# MCU_STM32F407ZGT6.net
KiCad netlist of a schematic drawn in Altium Designer
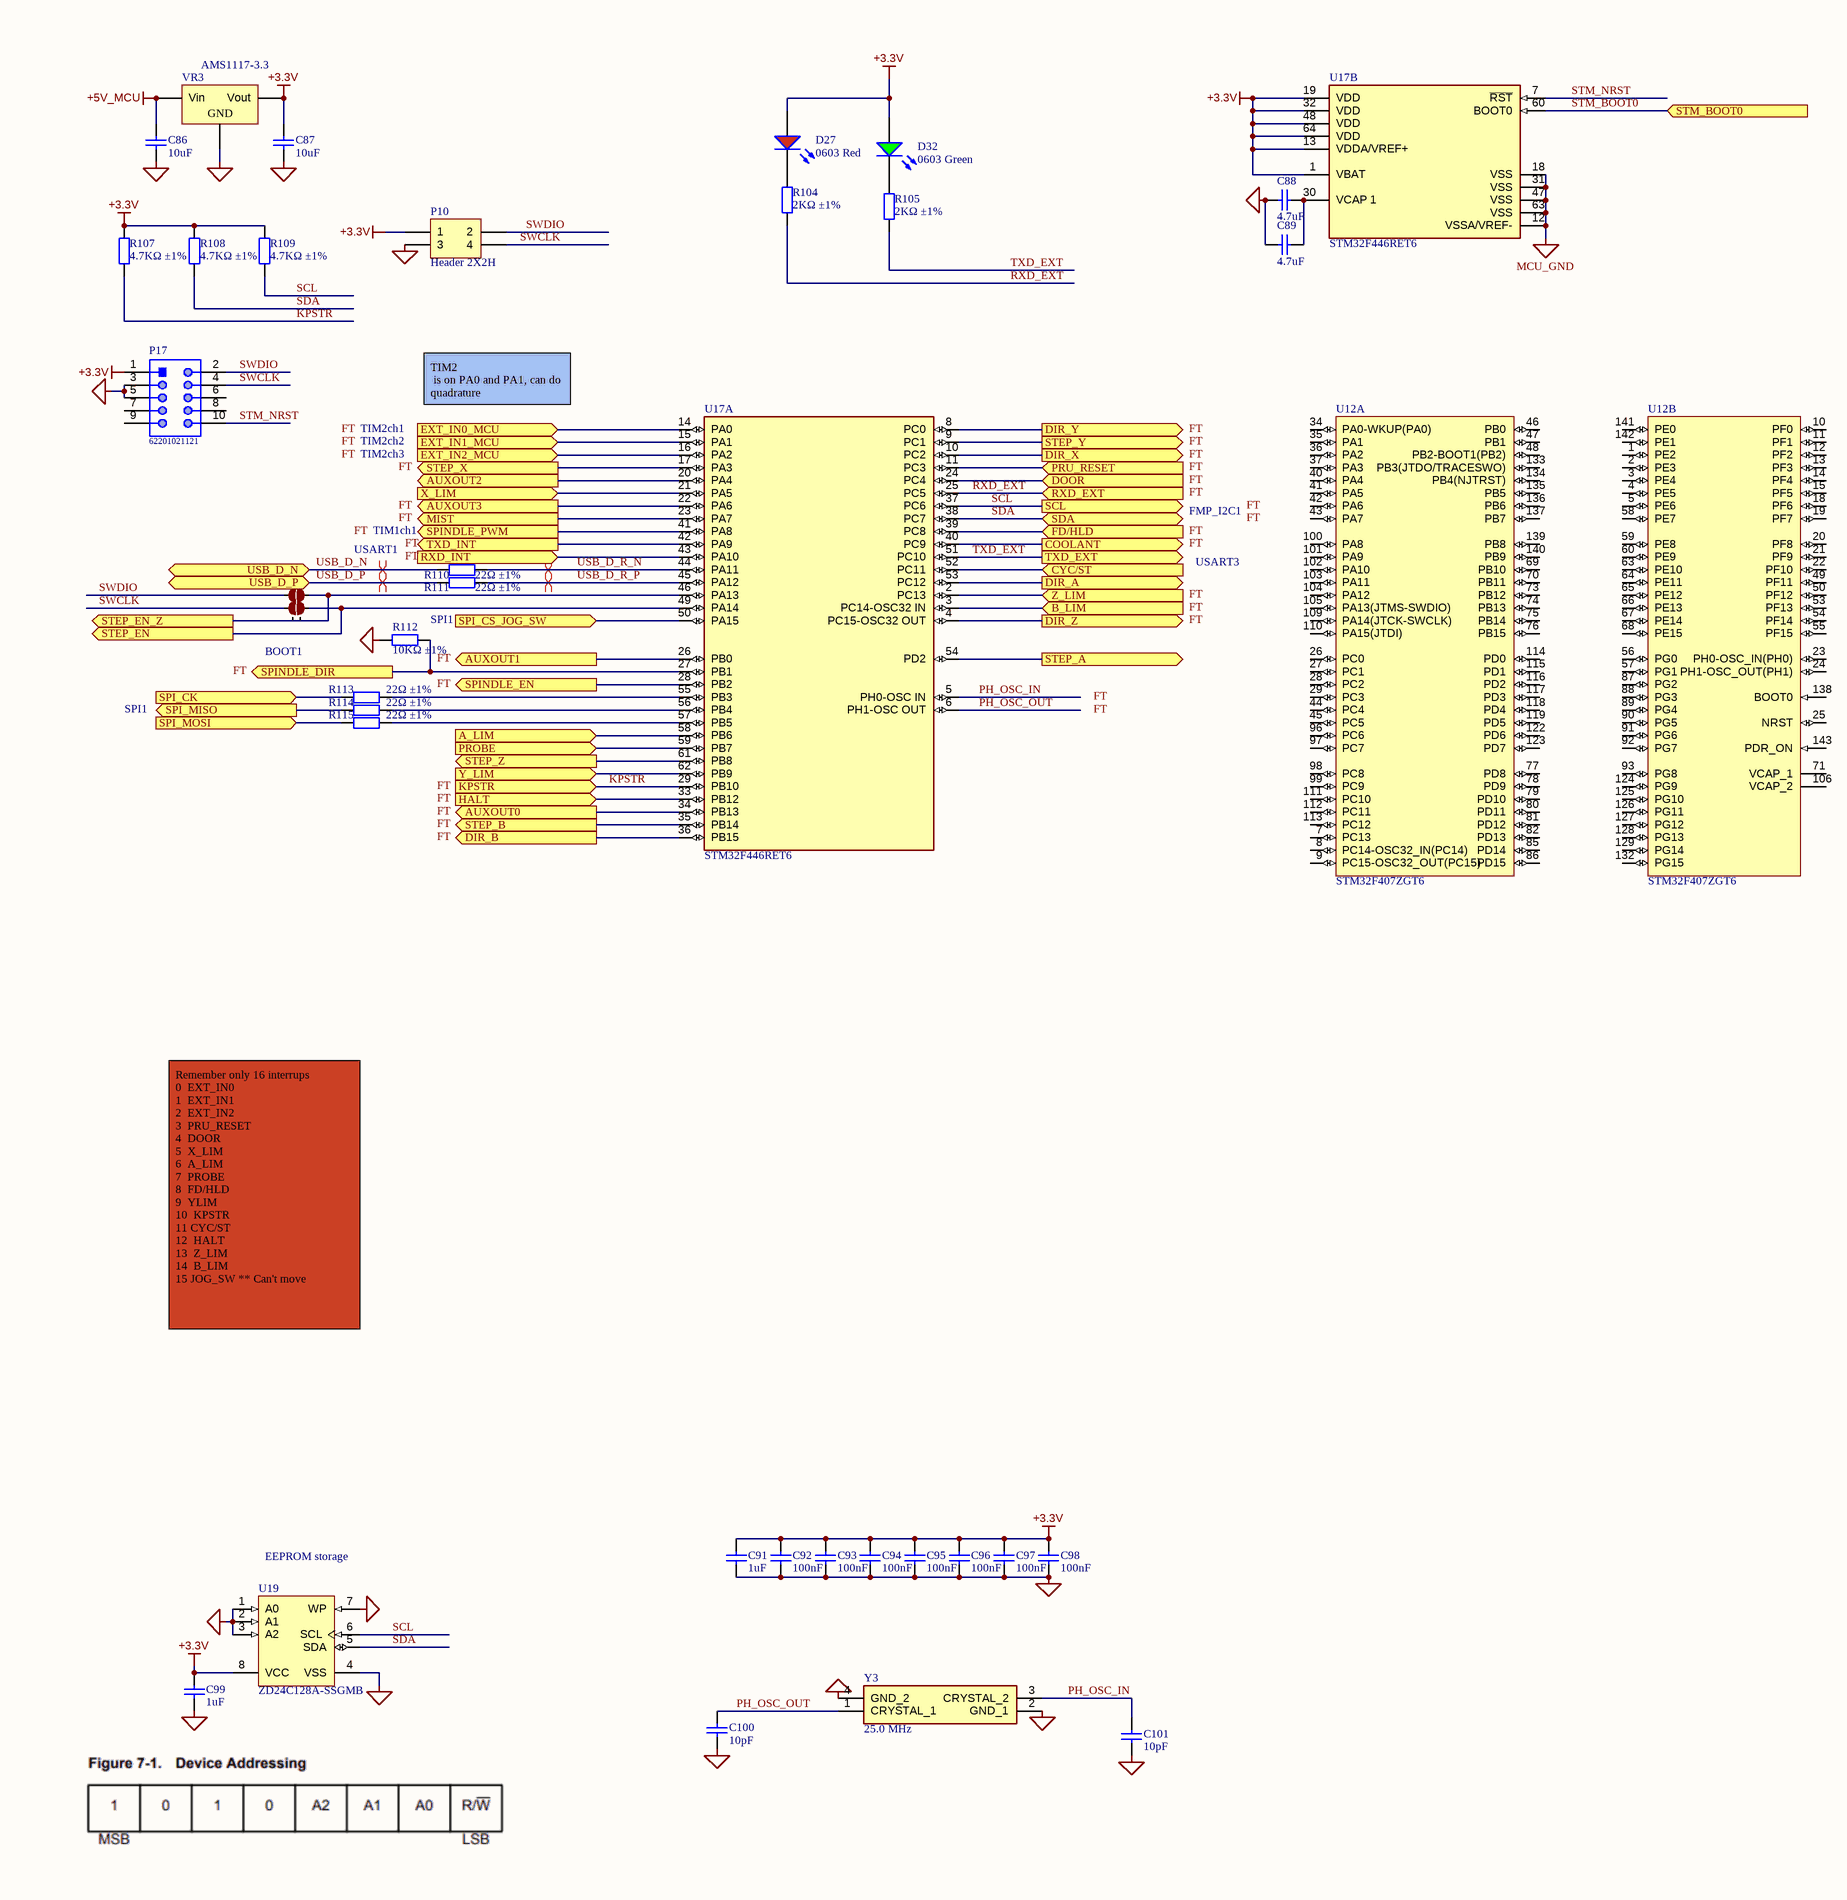
[diagram p0: MCU_STM32F407ZGT6.SchDoc, left]
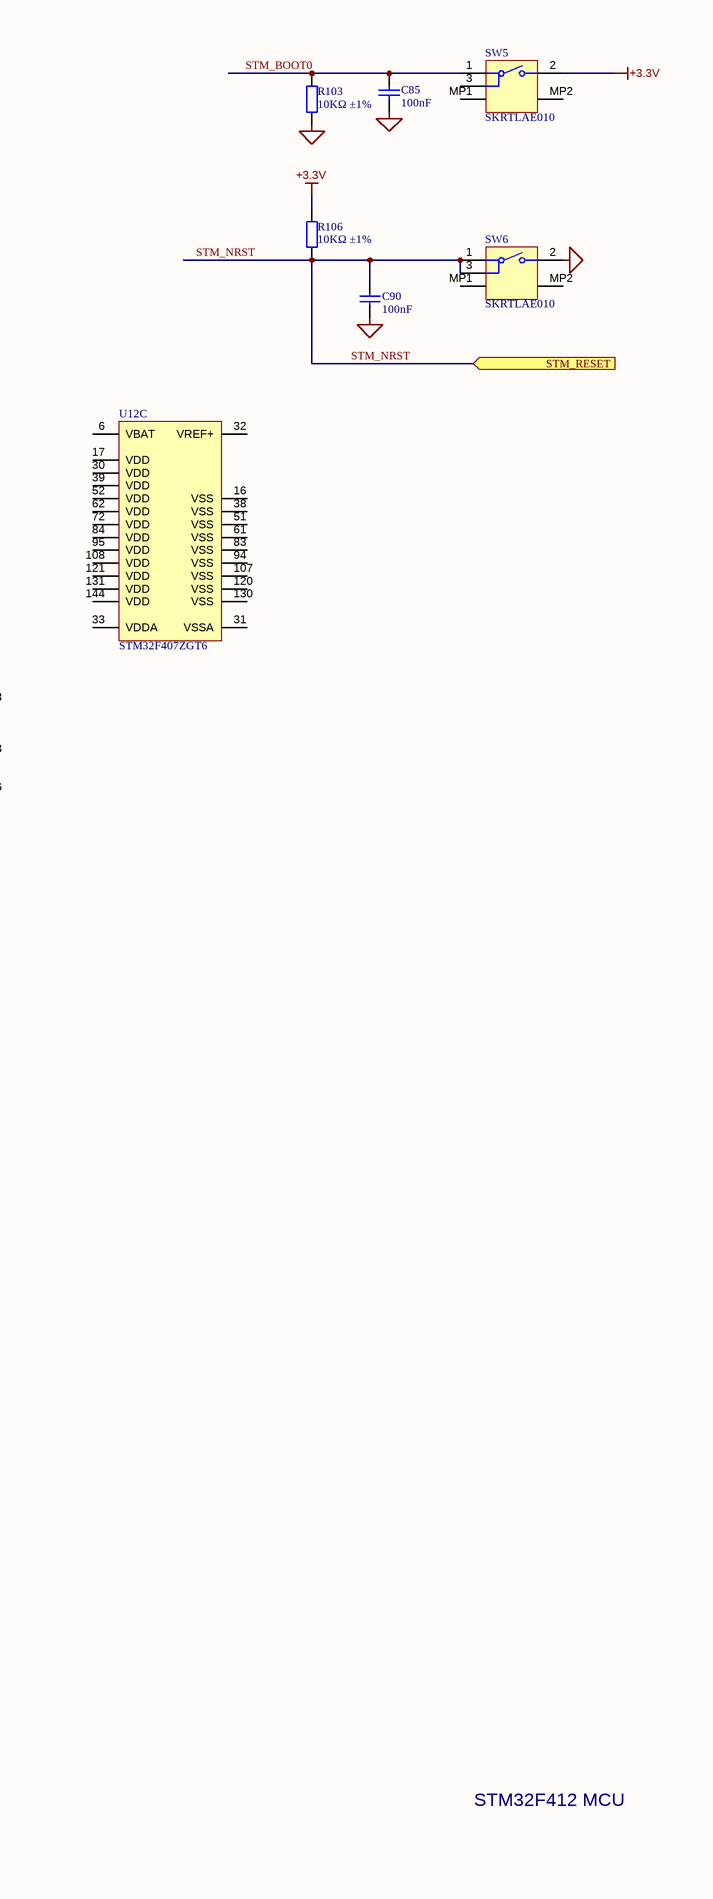
[diagram p1: MCU_STM32F407ZGT6.SchDoc, right]

(export (version "E")
  (design (tool "Eeschema 10.0.6"))
  (components
    (comp (ref "C85")
      (value "100nF")
      (footprint "0603_C")
      (description "Chip capacitors")
      (fields (field (name "MANUFACTURER") "YAGEO") (field (name "PARTNUMBER") "CC0603KRX7R9BB104"))
      (libsource (lib "Cap") (part "0603 100nF (104) 10% 50V"))
    )
    (comp (ref "C86")
      (value "10uF")
      (footprint "1206_C")
      (description "Chip capacitors")
      (fields
        (field (name "MANUFACTURER") "Samsung Electro-Mechanics")
        (field (name "PARTNUMBER") "CL31A106KBHNNNE")
      )
      (libsource (lib "Cap") (part "1206 10uF (106) 10% 50V"))
    )
    (comp (ref "C87")
      (value "10uF")
      (footprint "1206_C")
      (description "Chip capacitors")
      (fields
        (field (name "MANUFACTURER") "Samsung Electro-Mechanics")
        (field (name "PARTNUMBER") "CL31A106KBHNNNE")
      )
      (libsource (lib "Cap") (part "1206 10uF (106) 10% 50V"))
    )
    (comp (ref "C88")
      (value "4.7uF")
      (footprint "0603_C")
      (description "Chip capacitors")
      (fields
        (field (name "MANUFACTURER") "Samsung Electro-Mechanics")
        (field (name "PARTNUMBER") "CL10A475KO8NNNC")
      )
      (libsource (lib "Cap") (part "0603 4.7uF (475) 10% 16V"))
    )
    (comp (ref "C89")
      (value "4.7uF")
      (footprint "0603_C")
      (description "Chip capacitors")
      (fields
        (field (name "MANUFACTURER") "Samsung Electro-Mechanics")
        (field (name "PARTNUMBER") "CL10A475KO8NNNC")
      )
      (libsource (lib "Cap") (part "0603 4.7uF (475) 10% 16V"))
    )
    (comp (ref "C90")
      (value "100nF")
      (footprint "0603_C")
      (description "Chip capacitors")
      (fields (field (name "MANUFACTURER") "YAGEO") (field (name "PARTNUMBER") "CC0603KRX7R9BB104"))
      (libsource (lib "Cap") (part "0603 100nF (104) 10% 50V"))
    )
    (comp (ref "C91")
      (value "1uF")
      (footprint "0603_C")
      (description "Chip capacitors")
      (fields
        (field (name "MANUFACTURER") "Samsung Electro-Mechanics")
        (field (name "PARTNUMBER") "CL10A105KB8NNNC")
      )
      (libsource (lib "Cap") (part "0603 1uF (105) 10% 50V"))
    )
    (comp (ref "C92")
      (value "100nF")
      (footprint "0603_C")
      (description "Chip capacitors")
      (fields (field (name "MANUFACTURER") "YAGEO") (field (name "PARTNUMBER") "CC0603KRX7R9BB104"))
      (libsource (lib "Cap") (part "0603 100nF (104) 10% 50V"))
    )
    (comp (ref "C93")
      (value "100nF")
      (footprint "0603_C")
      (description "Chip capacitors")
      (fields (field (name "MANUFACTURER") "YAGEO") (field (name "PARTNUMBER") "CC0603KRX7R9BB104"))
      (libsource (lib "Cap") (part "0603 100nF (104) 10% 50V"))
    )
    (comp (ref "C94")
      (value "100nF")
      (footprint "0603_C")
      (description "Chip capacitors")
      (fields (field (name "MANUFACTURER") "YAGEO") (field (name "PARTNUMBER") "CC0603KRX7R9BB104"))
      (libsource (lib "Cap") (part "0603 100nF (104) 10% 50V"))
    )
    (comp (ref "C95")
      (value "100nF")
      (footprint "0603_C")
      (description "Chip capacitors")
      (fields (field (name "MANUFACTURER") "YAGEO") (field (name "PARTNUMBER") "CC0603KRX7R9BB104"))
      (libsource (lib "Cap") (part "0603 100nF (104) 10% 50V"))
    )
    (comp (ref "C96")
      (value "100nF")
      (footprint "0603_C")
      (description "Chip capacitors")
      (fields (field (name "MANUFACTURER") "YAGEO") (field (name "PARTNUMBER") "CC0603KRX7R9BB104"))
      (libsource (lib "Cap") (part "0603 100nF (104) 10% 50V"))
    )
    (comp (ref "C97")
      (value "100nF")
      (footprint "0603_C")
      (description "Chip capacitors")
      (fields (field (name "MANUFACTURER") "YAGEO") (field (name "PARTNUMBER") "CC0603KRX7R9BB104"))
      (libsource (lib "Cap") (part "0603 100nF (104) 10% 50V"))
    )
    (comp (ref "C98")
      (value "100nF")
      (footprint "0603_C")
      (description "Chip capacitors")
      (fields (field (name "MANUFACTURER") "YAGEO") (field (name "PARTNUMBER") "CC0603KRX7R9BB104"))
      (libsource (lib "Cap") (part "0603 100nF (104) 10% 50V"))
    )
    (comp (ref "C99")
      (value "1uF")
      (footprint "0603_C")
      (description "Chip capacitors")
      (fields
        (field (name "MANUFACTURER") "Samsung Electro-Mechanics")
        (field (name "PARTNUMBER") "CL10A105KB8NNNC")
      )
      (libsource (lib "Cap") (part "0603 1uF (105) 10% 50V"))
    )
    (comp (ref "C100")
      (value "10pF")
      (footprint "0603_C")
      (description "Chip capacitors")
      (fields
        (field (name "MANUFACTURER") "Samsung Electro-Mechanics")
        (field (name "PARTNUMBER") "CL10C100JB8NNNC")
      )
      (libsource (lib "Cap") (part "0603 10pF (100) 5% 50V"))
    )
    (comp (ref "C101")
      (value "10pF")
      (footprint "0603_C")
      (description "Chip capacitors")
      (fields
        (field (name "MANUFACTURER") "Samsung Electro-Mechanics")
        (field (name "PARTNUMBER") "CL10C100JB8NNNC")
      )
      (libsource (lib "Cap") (part "0603 10pF (100) 5% 50V"))
    )
    (comp (ref "D27")
      (value "0603 Red")
      (footprint "0603_LED_S1")
      (description "LED")
      (libsource (lib "LED") (part "0603 LED Red"))
    )
    (comp (ref "D32")
      (value "0603 Green")
      (footprint "0603_LED_S1")
      (description "LED")
      (libsource (lib "LED") (part "0603 LED Green"))
    )
    (comp (ref "J17")
      (value "2 way net solder junction - Normally Open")
      (footprint "2waySolder_NO")
      (libsource (lib "PrintNC_GRBLHAL_Breakout") (part "2waySolderNO"))
    )
    (comp (ref "J18")
      (value "2 way net solder junction - Normally Open")
      (footprint "2waySolder_NO")
      (libsource (lib "PrintNC_GRBLHAL_Breakout") (part "2waySolderNO"))
    )
    (comp (ref "P10")
      (value "Header 2X2H")
      (footprint "HDR2X2H")
      (description "Header, 2-Pin, Dual row, Right Angle")
      (fields (field (name "PUBLISHER") "Altium Limited"))
      (libsource (lib "Miscellaneous Connectors") (part "Header 2X2H"))
    )
    (comp (ref "P17")
      (value "62201021121")
      (footprint "62201021121")
      (description "THT Vertical Pin Header WR-PHD, Pitch 1.27 mm, Dual Row, 10 pins")
      (fields (field (name "MANUFACTURER") "Wurth Elektronik") (field (name "PUBLISHER") "WurthElektronik"))
      (libsource (lib "Altium Content Vault") (part "WE-CN-2P-M-R10"))
    )
    (comp (ref "R103")
      (value "10KΩ ±1%")
      (footprint "0603_R")
      (description "Chip resistor")
      (fields (field (name "MANUFACTURER") "Uniroyal Elec") (field (name "PARTNUMBER") "0603WAF1002T5E"))
      (libsource (lib "") (part "0603 10K (1002) 1%_1"))
    )
    (comp (ref "R104")
      (value "2KΩ ±1%")
      (footprint "0603_R")
      (description "Chip resistor")
      (fields (field (name "MANUFACTURER") "Uniroyal Elec") (field (name "PARTNUMBER") "0603WAF2001T5E"))
      (libsource (lib "RES") (part "0603 2K (2001) 1%"))
    )
    (comp (ref "R105")
      (value "2KΩ ±1%")
      (footprint "0603_R")
      (description "Chip resistor")
      (fields (field (name "MANUFACTURER") "Uniroyal Elec") (field (name "PARTNUMBER") "0603WAF2001T5E"))
      (libsource (lib "RES") (part "0603 2K (2001) 1%"))
    )
    (comp (ref "R106")
      (value "10KΩ ±1%")
      (footprint "0603_R")
      (description "Chip resistor")
      (fields (field (name "MANUFACTURER") "Uniroyal Elec") (field (name "PARTNUMBER") "0603WAF1002T5E"))
      (libsource (lib "") (part "0603 10K (1002) 1%_1"))
    )
    (comp (ref "R107")
      (value "4.7KΩ ±1%")
      (footprint "0603_R")
      (description "Chip resistor")
      (fields (field (name "MANUFACTURER") "Uniroyal Elec") (field (name "PARTNUMBER") "0603WAF4701T5E"))
      (libsource (lib "RES") (part "0603 4.7K (4701) 1%"))
    )
    (comp (ref "R108")
      (value "4.7KΩ ±1%")
      (footprint "0603_R")
      (description "Chip resistor")
      (fields (field (name "MANUFACTURER") "Uniroyal Elec") (field (name "PARTNUMBER") "0603WAF4701T5E"))
      (libsource (lib "RES") (part "0603 4.7K (4701) 1%"))
    )
    (comp (ref "R109")
      (value "4.7KΩ ±1%")
      (footprint "0603_R")
      (description "Chip resistor")
      (fields (field (name "MANUFACTURER") "Uniroyal Elec") (field (name "PARTNUMBER") "0603WAF4701T5E"))
      (libsource (lib "RES") (part "0603 4.7K (4701) 1%"))
    )
    (comp (ref "R110")
      (value "22Ω ±1%")
      (footprint "0603_R")
      (description "Chip resistor")
      (fields (field (name "MANUFACTURER") "Uniroyal Elec") (field (name "PARTNUMBER") "0603WAF220JT5E"))
      (libsource (lib "RES") (part "0603 22R (22R0) 1%"))
    )
    (comp (ref "R111")
      (value "22Ω ±1%")
      (footprint "0603_R")
      (description "Chip resistor")
      (fields (field (name "MANUFACTURER") "Uniroyal Elec") (field (name "PARTNUMBER") "0603WAF220JT5E"))
      (libsource (lib "RES") (part "0603 22R (22R0) 1%"))
    )
    (comp (ref "R112")
      (value "10KΩ ±1%")
      (footprint "0603_R")
      (description "Chip resistor")
      (fields (field (name "MANUFACTURER") "Uniroyal Elec") (field (name "PARTNUMBER") "0603WAF1002T5E"))
      (libsource (lib "RES") (part "0603 10K (1002) 1%"))
    )
    (comp (ref "R113")
      (value "22Ω ±1%")
      (footprint "0603_R")
      (description "Chip resistor")
      (fields (field (name "MANUFACTURER") "Uniroyal Elec") (field (name "PARTNUMBER") "0603WAF220JT5E"))
      (libsource (lib "RES") (part "0603 22R (22R0) 1%"))
    )
    (comp (ref "R114")
      (value "22Ω ±1%")
      (footprint "0603_R")
      (description "Chip resistor")
      (fields (field (name "MANUFACTURER") "Uniroyal Elec") (field (name "PARTNUMBER") "0603WAF220JT5E"))
      (libsource (lib "RES") (part "0603 22R (22R0) 1%"))
    )
    (comp (ref "R115")
      (value "22Ω ±1%")
      (footprint "0603_R")
      (description "Chip resistor")
      (fields (field (name "MANUFACTURER") "Uniroyal Elec") (field (name "PARTNUMBER") "0603WAF220JT5E"))
      (libsource (lib "RES") (part "0603 22R (22R0) 1%"))
    )
    (comp (ref "SW5")
      (value "SKRTLAE010")
      (footprint "ALPS-SKRTLAE010_V")
      (description "Side Push Type, 250 V, -40 to 90 degC, 3-Pin SMD, RoHS, Tape and Reel")
      (fields (field (name "MANUFACTURER") "ALPS"))
      (libsource (lib "Altium Content Vault") (part "SW_SPST-3_A"))
    )
    (comp (ref "SW6")
      (value "SKRTLAE010")
      (footprint "ALPS-SKRTLAE010_V")
      (description "Side Push Type, 250 V, -40 to 90 degC, 3-Pin SMD, RoHS, Tape and Reel")
      (fields (field (name "MANUFACTURER") "ALPS"))
      (libsource (lib "Altium Content Vault") (part "SW_SPST-3_A"))
    )
    (comp (ref "U12")
      (value "STM32F407ZGT6")
      (footprint "STM-LQFP144_L")
      (fields (field (name "MANUFACTURER") "STMicroelectronics") (field (name "PARTNUMBER") "STM32F407ZET6"))
      (libsource (lib "Universal_CNC_Breakout") (part "STM32F407ZGT6"))
    )
    (comp (ref "U17")
      (value "STM32F446RET6")
      (footprint "FP-LQFP64-5W-IPC_B")
      (description "IC MCU 32BIT 512KB FLASH 64LQFP")
      (fields
        (field (name "OCTOPART") "https://octopart.com/stm32f446ret6-stmicroelectronics-52642920")
        (field (name "MANUFACTURER") "STMicroelectronics")
      )
      (libsource (lib "Universal_CNC_Breakout") (part "STM32F446RET6"))
    )
    (comp (ref "U19")
      (value "ZD24C128A-SSGMB")
      (footprint "SOIC-SN8_L")
      (description "IC EEPROM 128KBIT I2C 8SOIC")
      (libsource (lib "PrintNC_GRBLHAL_Breakout") (part "MEM-SEEPROM-34AA02-IL8"))
    )
    (comp (ref "VR3")
      (value "AMS1117-3.3")
      (footprint "SOT-223")
      (description "Vout=3.3V 1A 72dB@(120Hz) (LDO)")
      (libsource (lib "LDO") (part "SOT-223 AMS1117-3.3"))
    )
    (comp (ref "Y3")
      (value "25.0 MHz")
      (footprint "SamacSys:YSX321SL")
      (description "Crystal or Oscillator")
      (fields (field (name "MANUFACTURER_PART_NUMBER") "X322525MSB4SI"))
      (libsource (lib "*") (part "YSX321SL"))
    )
  )
  (nets
    (net (code "1") (name "+3.3V") (class "Default")
      (node (ref "C87") (pin "2") (pinfunction "2_2") (pintype "passive"))
      (node (ref "C91") (pin "2") (pinfunction "2_2") (pintype "passive"))
      (node (ref "C92") (pin "2") (pinfunction "2_2") (pintype "passive"))
      (node (ref "C93") (pin "2") (pinfunction "2_2") (pintype "passive"))
      (node (ref "C94") (pin "2") (pinfunction "2_2") (pintype "passive"))
      (node (ref "C95") (pin "2") (pinfunction "2_2") (pintype "passive"))
      (node (ref "C96") (pin "2") (pinfunction "2_2") (pintype "passive"))
      (node (ref "C97") (pin "2") (pinfunction "2_2") (pintype "passive"))
      (node (ref "C98") (pin "2") (pinfunction "2_2") (pintype "passive"))
      (node (ref "C99") (pin "2") (pinfunction "2_2") (pintype "passive"))
      (node (ref "D27") (pin "A") (pinfunction "A_A") (pintype "passive"))
      (node (ref "D32") (pin "A") (pinfunction "A_A") (pintype "passive"))
      (node (ref "P10") (pin "1") (pinfunction "1_1") (pintype "passive"))
      (node (ref "P17") (pin "1") (pinfunction "1_1") (pintype "passive"))
      (node (ref "R106") (pin "1") (pinfunction "1_1") (pintype "passive"))
      (node (ref "R107") (pin "2") (pinfunction "2_2") (pintype "passive"))
      (node (ref "R108") (pin "2") (pinfunction "2_2") (pintype "passive"))
      (node (ref "R109") (pin "2") (pinfunction "2_2") (pintype "passive"))
      (node (ref "SW5") (pin "2") (pinfunction "2_2") (pintype "passive"))
      (node (ref "U17") (pin "1") (pinfunction "VBAT_1") (pintype "power_in"))
      (node (ref "U17") (pin "13") (pinfunction "VDDA/VREF+_13") (pintype "power_in"))
      (node (ref "U17") (pin "19") (pinfunction "VDD_19") (pintype "power_in"))
      (node (ref "U17") (pin "32") (pinfunction "VDD_32") (pintype "power_in"))
      (node (ref "U17") (pin "48") (pinfunction "VDD_48") (pintype "power_in"))
      (node (ref "U17") (pin "64") (pinfunction "VDD_64") (pintype "power_in"))
      (node (ref "U19") (pin "8") (pinfunction "VCC_8") (pintype "power_in"))
      (node (ref "VR3") (pin "2") (pinfunction "Vout_2") (pintype "passive"))
    )
    (net (code "2") (name "+5V_MCU") (class "Default")
      (node (ref "C86") (pin "2") (pinfunction "2_2") (pintype "passive"))
      (node (ref "VR3") (pin "3") (pinfunction "Vin_3") (pintype "passive"))
    )
    (net (code "3") (name "/AUXOUT0") (class "Default")
      (node (ref "U17") (pin "34") (pinfunction "PB13_34") (pintype "bidirectional"))
    )
    (net (code "4") (name "/AUXOUT1") (class "Default")
      (node (ref "U17") (pin "26") (pinfunction "PB0_26") (pintype "bidirectional"))
    )
    (net (code "5") (name "/AUXOUT2") (class "Default")
      (node (ref "U17") (pin "20") (pinfunction "PA4_20") (pintype "bidirectional"))
    )
    (net (code "6") (name "/AUXOUT3") (class "Default")
      (node (ref "U17") (pin "22") (pinfunction "PA6_22") (pintype "bidirectional"))
    )
    (net (code "7") (name "/A_LIM") (class "Default")
      (node (ref "U17") (pin "58") (pinfunction "PB6_58") (pintype "bidirectional"))
    )
    (net (code "8") (name "/B_LIM") (class "Default")
      (node (ref "U17") (pin "3") (pinfunction "PC14-OSC32_IN_3") (pintype "bidirectional"))
    )
    (net (code "9") (name "/COOLANT") (class "Default")
      (node (ref "U17") (pin "40") (pinfunction "PC9_40") (pintype "bidirectional"))
    )
    (net (code "10") (name "/CYC{slash}ST") (class "Default")
      (node (ref "U17") (pin "52") (pinfunction "PC11_52") (pintype "bidirectional"))
    )
    (net (code "11") (name "/DIR_A") (class "Default")
      (node (ref "U17") (pin "53") (pinfunction "PC12_53") (pintype "bidirectional"))
    )
    (net (code "12") (name "/DIR_B") (class "Default")
      (node (ref "U17") (pin "36") (pinfunction "PB15_36") (pintype "bidirectional"))
    )
    (net (code "13") (name "/DIR_X") (class "Default")
      (node (ref "U17") (pin "10") (pinfunction "PC2_10") (pintype "bidirectional"))
    )
    (net (code "14") (name "/DIR_Y") (class "Default")
      (node (ref "U17") (pin "8") (pinfunction "PC0_8") (pintype "bidirectional"))
    )
    (net (code "15") (name "/DIR_Z") (class "Default")
      (node (ref "U17") (pin "4") (pinfunction "PC15-OSC32_OUT_4") (pintype "bidirectional"))
    )
    (net (code "16") (name "/DOOR") (class "Default")
      (node (ref "U17") (pin "24") (pinfunction "PC4_24") (pintype "bidirectional"))
    )
    (net (code "17") (name "/EXT_IN0_MCU") (class "Default")
      (node (ref "U17") (pin "14") (pinfunction "PA0_14") (pintype "bidirectional"))
    )
    (net (code "18") (name "/EXT_IN1_MCU") (class "Default")
      (node (ref "U17") (pin "15") (pinfunction "PA1_15") (pintype "bidirectional"))
    )
    (net (code "19") (name "/EXT_IN2_MCU") (class "Default")
      (node (ref "U17") (pin "16") (pinfunction "PA2_16") (pintype "bidirectional"))
    )
    (net (code "20") (name "/FD{slash}HLD") (class "Default")
      (node (ref "U17") (pin "39") (pinfunction "PC8_39") (pintype "bidirectional"))
    )
    (net (code "21") (name "/HALT") (class "Default")
      (node (ref "U17") (pin "33") (pinfunction "PB12_33") (pintype "bidirectional"))
    )
    (net (code "22") (name "/KPSTR") (class "Default")
      (node (ref "R107") (pin "1") (pinfunction "1_1") (pintype "passive"))
      (node (ref "U17") (pin "29") (pinfunction "PB10_29") (pintype "bidirectional"))
    )
    (net (code "23") (name "/MIST") (class "Default")
      (node (ref "U17") (pin "23") (pinfunction "PA7_23") (pintype "bidirectional"))
    )
    (net (code "24") (name "/PH_OSC_IN") (class "Default")
      (node (ref "C101") (pin "2") (pinfunction "2_2") (pintype "passive"))
      (node (ref "U17") (pin "5") (pinfunction "PH0-OSC_IN_5") (pintype "bidirectional"))
      (node (ref "Y3") (pin "3") (pinfunction "CRYSTAL_2_3") (pintype "passive"))
    )
    (net (code "25") (name "/PH_OSC_OUT") (class "Default")
      (node (ref "C100") (pin "2") (pinfunction "2_2") (pintype "passive"))
      (node (ref "U17") (pin "6") (pinfunction "PH1-OSC_OUT_6") (pintype "bidirectional"))
      (node (ref "Y3") (pin "1") (pinfunction "CRYSTAL_1_1") (pintype "passive"))
    )
    (net (code "26") (name "/PROBE") (class "Default")
      (node (ref "U17") (pin "59") (pinfunction "PB7_59") (pintype "bidirectional"))
    )
    (net (code "27") (name "/PRU_RESET") (class "Default")
      (node (ref "U17") (pin "11") (pinfunction "PC3_11") (pintype "bidirectional"))
    )
    (net (code "28") (name "/RXD_EXT") (class "Default")
      (node (ref "R104") (pin "1") (pinfunction "1_1") (pintype "passive"))
      (node (ref "U17") (pin "25") (pinfunction "PC5_25") (pintype "bidirectional"))
    )
    (net (code "29") (name "/RXD_INT") (class "Default")
      (node (ref "U17") (pin "43") (pinfunction "PA10_43") (pintype "bidirectional"))
    )
    (net (code "30") (name "/SCL") (class "Default")
      (node (ref "R109") (pin "1") (pinfunction "1_1") (pintype "passive"))
      (node (ref "U17") (pin "37") (pinfunction "PC6_37") (pintype "bidirectional"))
      (node (ref "U19") (pin "6") (pinfunction "SCL_6") (pintype "input"))
    )
    (net (code "31") (name "/SDA") (class "Default")
      (node (ref "R108") (pin "1") (pinfunction "1_1") (pintype "passive"))
      (node (ref "U17") (pin "38") (pinfunction "PC7_38") (pintype "bidirectional"))
      (node (ref "U19") (pin "5") (pinfunction "SDA_5") (pintype "bidirectional"))
    )
    (net (code "32") (name "/SPINDLE_DIR") (class "Default")
      (node (ref "R112") (pin "2") (pinfunction "2_2") (pintype "passive"))
      (node (ref "U17") (pin "27") (pinfunction "PB1_27") (pintype "bidirectional"))
    )
    (net (code "33") (name "/SPINDLE_EN") (class "Default")
      (node (ref "U17") (pin "28") (pinfunction "PB2_28") (pintype "bidirectional"))
    )
    (net (code "34") (name "/SPINDLE_PWM") (class "Default")
      (node (ref "U17") (pin "41") (pinfunction "PA8_41") (pintype "bidirectional"))
    )
    (net (code "35") (name "/SPI_CK") (class "Default")
      (node (ref "R113") (pin "2") (pinfunction "2_2") (pintype "passive"))
    )
    (net (code "36") (name "/SPI_CS_JOG_SW") (class "Default")
      (node (ref "U17") (pin "50") (pinfunction "PA15_50") (pintype "bidirectional"))
    )
    (net (code "37") (name "/SPI_MISO") (class "Default")
      (node (ref "R114") (pin "2") (pinfunction "2_2") (pintype "passive"))
    )
    (net (code "38") (name "/SPI_MOSI") (class "Default")
      (node (ref "R115") (pin "2") (pinfunction "2_2") (pintype "passive"))
    )
    (net (code "39") (name "/STEP_A") (class "Default")
      (node (ref "U17") (pin "54") (pinfunction "PD2_54") (pintype "bidirectional"))
    )
    (net (code "40") (name "/STEP_B") (class "Default")
      (node (ref "U17") (pin "35") (pinfunction "PB14_35") (pintype "bidirectional"))
    )
    (net (code "41") (name "/STEP_EN") (class "Default")
      (node (ref "J18") (pin "2") (pinfunction "2_2") (pintype "passive"))
      (node (ref "U17") (pin "49") (pinfunction "PA14_49") (pintype "bidirectional"))
    )
    (net (code "42") (name "/STEP_EN_Z") (class "Default")
      (node (ref "J17") (pin "2") (pinfunction "2_2") (pintype "passive"))
      (node (ref "U17") (pin "46") (pinfunction "PA13_46") (pintype "bidirectional"))
    )
    (net (code "43") (name "/STEP_X") (class "Default")
      (node (ref "U17") (pin "17") (pinfunction "PA3_17") (pintype "bidirectional"))
    )
    (net (code "44") (name "/STEP_Y") (class "Default")
      (node (ref "U17") (pin "9") (pinfunction "PC1_9") (pintype "bidirectional"))
    )
    (net (code "45") (name "/STEP_Z") (class "Default")
      (node (ref "U17") (pin "61") (pinfunction "PB8_61") (pintype "bidirectional"))
    )
    (net (code "46") (name "/STM_BOOT0") (class "Default")
      (node (ref "C85") (pin "2") (pinfunction "2_2") (pintype "passive"))
      (node (ref "R103") (pin "1") (pinfunction "1_1") (pintype "passive"))
      (node (ref "SW5") (pin "1") (pinfunction "1_1") (pintype "passive"))
      (node (ref "U17") (pin "60") (pinfunction "BOOT0_60") (pintype "input"))
    )
    (net (code "47") (name "/STM_NRST") (class "Default")
      (node (ref "C90") (pin "2") (pinfunction "2_2") (pintype "passive"))
      (node (ref "P17") (pin "10") (pinfunction "10_10") (pintype "passive"))
      (node (ref "R106") (pin "2") (pinfunction "2_2") (pintype "passive"))
      (node (ref "SW6") (pin "1") (pinfunction "1_1") (pintype "passive"))
      (node (ref "SW6") (pin "3") (pinfunction "3_3") (pintype "passive"))
      (node (ref "U17") (pin "7") (pinfunction "~{RST}_7") (pintype "input"))
    )
    (net (code "48") (name "/SWCLK") (class "Default")
      (node (ref "J18") (pin "1") (pinfunction "1_1") (pintype "passive"))
      (node (ref "P10") (pin "4") (pinfunction "4_4") (pintype "passive"))
      (node (ref "P17") (pin "4") (pinfunction "4_4") (pintype "passive"))
    )
    (net (code "49") (name "/SWDIO") (class "Default")
      (node (ref "J17") (pin "1") (pinfunction "1_1") (pintype "passive"))
      (node (ref "P10") (pin "2") (pinfunction "2_2") (pintype "passive"))
      (node (ref "P17") (pin "2") (pinfunction "2_2") (pintype "passive"))
    )
    (net (code "50") (name "/TXD_EXT") (class "Default")
      (node (ref "R105") (pin "1") (pinfunction "1_1") (pintype "passive"))
      (node (ref "U17") (pin "51") (pinfunction "PC10_51") (pintype "bidirectional"))
    )
    (net (code "51") (name "/TXD_INT") (class "Default")
      (node (ref "U17") (pin "42") (pinfunction "PA9_42") (pintype "bidirectional"))
    )
    (net (code "52") (name "/USB_D_N") (class "Default")
      (node (ref "R110") (pin "2") (pinfunction "2_2") (pintype "passive"))
    )
    (net (code "53") (name "/USB_D_P") (class "Default")
      (node (ref "R111") (pin "2") (pinfunction "2_2") (pintype "passive"))
    )
    (net (code "54") (name "/USB_D_R_N") (class "Default")
      (node (ref "R110") (pin "1") (pinfunction "1_1") (pintype "passive"))
      (node (ref "U17") (pin "44") (pinfunction "PA11_44") (pintype "bidirectional"))
    )
    (net (code "55") (name "/USB_D_R_P") (class "Default")
      (node (ref "R111") (pin "1") (pinfunction "1_1") (pintype "passive"))
      (node (ref "U17") (pin "45") (pinfunction "PA12_45") (pintype "bidirectional"))
    )
    (net (code "56") (name "/X_LIM") (class "Default")
      (node (ref "U17") (pin "21") (pinfunction "PA5_21") (pintype "bidirectional"))
    )
    (net (code "57") (name "/Y_LIM") (class "Default")
      (node (ref "U17") (pin "62") (pinfunction "PB9_62") (pintype "bidirectional"))
    )
    (net (code "58") (name "/Z_LIM") (class "Default")
      (node (ref "U17") (pin "2") (pinfunction "PC13_2") (pintype "bidirectional"))
    )
    (net (code "59") (name "MCU_GND") (class "Default")
      (node (ref "C100") (pin "1") (pinfunction "1_1") (pintype "passive"))
      (node (ref "C101") (pin "1") (pinfunction "1_1") (pintype "passive"))
      (node (ref "C85") (pin "1") (pinfunction "1_1") (pintype "passive"))
      (node (ref "C86") (pin "1") (pinfunction "1_1") (pintype "passive"))
      (node (ref "C87") (pin "1") (pinfunction "1_1") (pintype "passive"))
      (node (ref "C88") (pin "1") (pinfunction "1_1") (pintype "passive"))
      (node (ref "C89") (pin "1") (pinfunction "1_1") (pintype "passive"))
      (node (ref "C90") (pin "1") (pinfunction "1_1") (pintype "passive"))
      (node (ref "C91") (pin "1") (pinfunction "1_1") (pintype "passive"))
      (node (ref "C92") (pin "1") (pinfunction "1_1") (pintype "passive"))
      (node (ref "C93") (pin "1") (pinfunction "1_1") (pintype "passive"))
      (node (ref "C94") (pin "1") (pinfunction "1_1") (pintype "passive"))
      (node (ref "C95") (pin "1") (pinfunction "1_1") (pintype "passive"))
      (node (ref "C96") (pin "1") (pinfunction "1_1") (pintype "passive"))
      (node (ref "C97") (pin "1") (pinfunction "1_1") (pintype "passive"))
      (node (ref "C98") (pin "1") (pinfunction "1_1") (pintype "passive"))
      (node (ref "C99") (pin "1") (pinfunction "1_1") (pintype "passive"))
      (node (ref "P10") (pin "3") (pinfunction "3_3") (pintype "passive"))
      (node (ref "P17") (pin "3") (pinfunction "3_3") (pintype "passive"))
      (node (ref "P17") (pin "5") (pinfunction "5_5") (pintype "passive"))
      (node (ref "R103") (pin "2") (pinfunction "2_2") (pintype "passive"))
      (node (ref "R112") (pin "1") (pinfunction "1_1") (pintype "passive"))
      (node (ref "SW6") (pin "2") (pinfunction "2_2") (pintype "passive"))
      (node (ref "U17") (pin "12") (pinfunction "VSSA/VREF-_12") (pintype "power_in"))
      (node (ref "U17") (pin "18") (pinfunction "VSS_18") (pintype "power_in"))
      (node (ref "U17") (pin "31") (pinfunction "VSS_31") (pintype "power_in"))
      (node (ref "U17") (pin "47") (pinfunction "VSS_47") (pintype "power_in"))
      (node (ref "U17") (pin "63") (pinfunction "VSS_63") (pintype "power_in"))
      (node (ref "U19") (pin "1") (pinfunction "A0_1") (pintype "input"))
      (node (ref "U19") (pin "2") (pinfunction "A1_2") (pintype "input"))
      (node (ref "U19") (pin "3") (pinfunction "A2_3") (pintype "input"))
      (node (ref "U19") (pin "4") (pinfunction "VSS_4") (pintype "power_in"))
      (node (ref "U19") (pin "7") (pinfunction "WP_7") (pintype "input"))
      (node (ref "VR3") (pin "1") (pinfunction "GND_1") (pintype "passive"))
      (node (ref "Y3") (pin "2") (pinfunction "GND_1_2") (pintype "passive"))
      (node (ref "Y3") (pin "4") (pinfunction "GND_2_4") (pintype "passive"))
    )
    (net (code "60") (name "Net-(D27-PadK)") (class "Default")
      (node (ref "D27") (pin "K") (pinfunction "K_K") (pintype "passive"))
      (node (ref "R104") (pin "2") (pinfunction "2_2") (pintype "passive"))
    )
    (net (code "61") (name "Net-(D32-PadK)") (class "Default")
      (node (ref "D32") (pin "K") (pinfunction "K_K") (pintype "passive"))
      (node (ref "R105") (pin "2") (pinfunction "2_2") (pintype "passive"))
    )
    (net (code "62") (name "Net-(U17A-PB3)") (class "Default")
      (node (ref "R113") (pin "1") (pinfunction "1_1") (pintype "passive"))
      (node (ref "U17") (pin "55") (pinfunction "PB3_55") (pintype "bidirectional"))
    )
    (net (code "63") (name "Net-(U17A-PB4)") (class "Default")
      (node (ref "R114") (pin "1") (pinfunction "1_1") (pintype "passive"))
      (node (ref "U17") (pin "56") (pinfunction "PB4_56") (pintype "bidirectional"))
    )
    (net (code "64") (name "Net-(U17A-PB5)") (class "Default")
      (node (ref "R115") (pin "1") (pinfunction "1_1") (pintype "passive"))
      (node (ref "U17") (pin "57") (pinfunction "PB5_57") (pintype "bidirectional"))
    )
    (net (code "65") (name "Net-(U17B-VCAP_1)") (class "Default")
      (node (ref "C88") (pin "2") (pinfunction "2_2") (pintype "passive"))
      (node (ref "C89") (pin "2") (pinfunction "2_2") (pintype "passive"))
      (node (ref "U17") (pin "30") (pinfunction "VCAP_1_30") (pintype "power_in"))
    )
    (net (code "66") (name "unconnected-(P17-Pad6)") (class "Default")
      (node (ref "P17") (pin "6") (pinfunction "6_6") (pintype "passive"))
    )
    (net (code "67") (name "unconnected-(P17-Pad7)") (class "Default")
      (node (ref "P17") (pin "7") (pinfunction "7_7") (pintype "passive"))
    )
    (net (code "68") (name "unconnected-(P17-Pad8)") (class "Default")
      (node (ref "P17") (pin "8") (pinfunction "8_8") (pintype "passive"))
    )
    (net (code "69") (name "unconnected-(P17-Pad9)") (class "Default")
      (node (ref "P17") (pin "9") (pinfunction "9_9") (pintype "passive"))
    )
    (net (code "70") (name "unconnected-(SW5-Pad3)") (class "Default")
      (node (ref "SW5") (pin "3") (pinfunction "3_3") (pintype "passive"))
    )
    (net (code "71") (name "unconnected-(SW5-PadMP1)") (class "Default")
      (node (ref "SW5") (pin "MP1") (pinfunction "MP1_MP1") (pintype "passive"))
    )
    (net (code "72") (name "unconnected-(SW5-PadMP2)") (class "Default")
      (node (ref "SW5") (pin "MP2") (pinfunction "MP2_MP2") (pintype "passive"))
    )
    (net (code "73") (name "unconnected-(SW6-PadMP1)") (class "Default")
      (node (ref "SW6") (pin "MP1") (pinfunction "MP1_MP1") (pintype "passive"))
    )
    (net (code "74") (name "unconnected-(SW6-PadMP2)") (class "Default")
      (node (ref "SW6") (pin "MP2") (pinfunction "MP2_MP2") (pintype "passive"))
    )
    (net (code "75") (name "unconnected-(U12A-PA0-WKUP(PA0)-Pad34)") (class "Default")
      (node (ref "U12") (pin "34") (pinfunction "PA0-WKUP(PA0)_34") (pintype "bidirectional"))
    )
    (net (code "76") (name "unconnected-(U12A-PA1-Pad35)") (class "Default")
      (node (ref "U12") (pin "35") (pinfunction "PA1_35") (pintype "bidirectional"))
    )
    (net (code "77") (name "unconnected-(U12A-PA2-Pad36)") (class "Default")
      (node (ref "U12") (pin "36") (pinfunction "PA2_36") (pintype "bidirectional"))
    )
    (net (code "78") (name "unconnected-(U12A-PA3-Pad37)") (class "Default")
      (node (ref "U12") (pin "37") (pinfunction "PA3_37") (pintype "bidirectional"))
    )
    (net (code "79") (name "unconnected-(U12A-PA4-Pad40)") (class "Default")
      (node (ref "U12") (pin "40") (pinfunction "PA4_40") (pintype "bidirectional"))
    )
    (net (code "80") (name "unconnected-(U12A-PA5-Pad41)") (class "Default")
      (node (ref "U12") (pin "41") (pinfunction "PA5_41") (pintype "bidirectional"))
    )
    (net (code "81") (name "unconnected-(U12A-PA6-Pad42)") (class "Default")
      (node (ref "U12") (pin "42") (pinfunction "PA6_42") (pintype "bidirectional"))
    )
    (net (code "82") (name "unconnected-(U12A-PA7-Pad43)") (class "Default")
      (node (ref "U12") (pin "43") (pinfunction "PA7_43") (pintype "bidirectional"))
    )
    (net (code "83") (name "unconnected-(U12A-PA8-Pad100)") (class "Default")
      (node (ref "U12") (pin "100") (pinfunction "PA8_100") (pintype "bidirectional"))
    )
    (net (code "84") (name "unconnected-(U12A-PA9-Pad101)") (class "Default")
      (node (ref "U12") (pin "101") (pinfunction "PA9_101") (pintype "bidirectional"))
    )
    (net (code "85") (name "unconnected-(U12A-PA10-Pad102)") (class "Default")
      (node (ref "U12") (pin "102") (pinfunction "PA10_102") (pintype "bidirectional"))
    )
    (net (code "86") (name "unconnected-(U12A-PA11-Pad103)") (class "Default")
      (node (ref "U12") (pin "103") (pinfunction "PA11_103") (pintype "bidirectional"))
    )
    (net (code "87") (name "unconnected-(U12A-PA12-Pad104)") (class "Default")
      (node (ref "U12") (pin "104") (pinfunction "PA12_104") (pintype "bidirectional"))
    )
    (net (code "88") (name "unconnected-(U12A-PA13(JTMS-SWDIO)-Pad105)") (class "Default")
      (node (ref "U12") (pin "105") (pinfunction "PA13(JTMS-SWDIO)_105") (pintype "bidirectional"))
    )
    (net (code "89") (name "unconnected-(U12A-PA14(JTCK-SWCLK)-Pad109)") (class "Default")
      (node (ref "U12") (pin "109") (pinfunction "PA14(JTCK-SWCLK)_109") (pintype "bidirectional"))
    )
    (net (code "90") (name "unconnected-(U12A-PA15(JTDI)-Pad110)") (class "Default")
      (node (ref "U12") (pin "110") (pinfunction "PA15(JTDI)_110") (pintype "bidirectional"))
    )
    (net (code "91") (name "unconnected-(U12A-PB0-Pad46)") (class "Default")
      (node (ref "U12") (pin "46") (pinfunction "PB0_46") (pintype "bidirectional"))
    )
    (net (code "92") (name "unconnected-(U12A-PB1-Pad47)") (class "Default")
      (node (ref "U12") (pin "47") (pinfunction "PB1_47") (pintype "bidirectional"))
    )
    (net (code "93") (name "unconnected-(U12A-PB2-BOOT1(PB2)-Pad48)") (class "Default")
      (node (ref "U12") (pin "48") (pinfunction "PB2-BOOT1(PB2)_48") (pintype "bidirectional"))
    )
    (net (code "94") (name "unconnected-(U12A-PB3(JTDO{slash}TRACESWO)-Pad133)") (class "Default")
      (node (ref "U12") (pin "133") (pinfunction "PB3(JTDO/TRACESWO)_133") (pintype "bidirectional"))
    )
    (net (code "95") (name "unconnected-(U12A-PB4(NJTRST)-Pad134)") (class "Default")
      (node (ref "U12") (pin "134") (pinfunction "PB4(NJTRST)_134") (pintype "bidirectional"))
    )
    (net (code "96") (name "unconnected-(U12A-PB5-Pad135)") (class "Default")
      (node (ref "U12") (pin "135") (pinfunction "PB5_135") (pintype "bidirectional"))
    )
    (net (code "97") (name "unconnected-(U12A-PB6-Pad136)") (class "Default")
      (node (ref "U12") (pin "136") (pinfunction "PB6_136") (pintype "bidirectional"))
    )
    (net (code "98") (name "unconnected-(U12A-PB7-Pad137)") (class "Default")
      (node (ref "U12") (pin "137") (pinfunction "PB7_137") (pintype "bidirectional"))
    )
    (net (code "99") (name "unconnected-(U12A-PB8-Pad139)") (class "Default")
      (node (ref "U12") (pin "139") (pinfunction "PB8_139") (pintype "bidirectional"))
    )
    (net (code "100") (name "unconnected-(U12A-PB9-Pad140)") (class "Default")
      (node (ref "U12") (pin "140") (pinfunction "PB9_140") (pintype "bidirectional"))
    )
    (net (code "101") (name "unconnected-(U12A-PB10-Pad69)") (class "Default")
      (node (ref "U12") (pin "69") (pinfunction "PB10_69") (pintype "bidirectional"))
    )
    (net (code "102") (name "unconnected-(U12A-PB11-Pad70)") (class "Default")
      (node (ref "U12") (pin "70") (pinfunction "PB11_70") (pintype "bidirectional"))
    )
    (net (code "103") (name "unconnected-(U12A-PB12-Pad73)") (class "Default")
      (node (ref "U12") (pin "73") (pinfunction "PB12_73") (pintype "bidirectional"))
    )
    (net (code "104") (name "unconnected-(U12A-PB13-Pad74)") (class "Default")
      (node (ref "U12") (pin "74") (pinfunction "PB13_74") (pintype "bidirectional"))
    )
    (net (code "105") (name "unconnected-(U12A-PB14-Pad75)") (class "Default")
      (node (ref "U12") (pin "75") (pinfunction "PB14_75") (pintype "bidirectional"))
    )
    (net (code "106") (name "unconnected-(U12A-PB15-Pad76)") (class "Default")
      (node (ref "U12") (pin "76") (pinfunction "PB15_76") (pintype "bidirectional"))
    )
    (net (code "107") (name "unconnected-(U12A-PC0-Pad26)") (class "Default")
      (node (ref "U12") (pin "26") (pinfunction "PC0_26") (pintype "bidirectional"))
    )
    (net (code "108") (name "unconnected-(U12A-PC1-Pad27)") (class "Default")
      (node (ref "U12") (pin "27") (pinfunction "PC1_27") (pintype "bidirectional"))
    )
    (net (code "109") (name "unconnected-(U12A-PC2-Pad28)") (class "Default")
      (node (ref "U12") (pin "28") (pinfunction "PC2_28") (pintype "bidirectional"))
    )
    (net (code "110") (name "unconnected-(U12A-PC3-Pad29)") (class "Default")
      (node (ref "U12") (pin "29") (pinfunction "PC3_29") (pintype "bidirectional"))
    )
    (net (code "111") (name "unconnected-(U12A-PC4-Pad44)") (class "Default")
      (node (ref "U12") (pin "44") (pinfunction "PC4_44") (pintype "bidirectional"))
    )
    (net (code "112") (name "unconnected-(U12A-PC5-Pad45)") (class "Default")
      (node (ref "U12") (pin "45") (pinfunction "PC5_45") (pintype "bidirectional"))
    )
    (net (code "113") (name "unconnected-(U12A-PC6-Pad96)") (class "Default")
      (node (ref "U12") (pin "96") (pinfunction "PC6_96") (pintype "bidirectional"))
    )
    (net (code "114") (name "unconnected-(U12A-PC7-Pad97)") (class "Default")
      (node (ref "U12") (pin "97") (pinfunction "PC7_97") (pintype "bidirectional"))
    )
    (net (code "115") (name "unconnected-(U12A-PC8-Pad98)") (class "Default")
      (node (ref "U12") (pin "98") (pinfunction "PC8_98") (pintype "bidirectional"))
    )
    (net (code "116") (name "unconnected-(U12A-PC9-Pad99)") (class "Default")
      (node (ref "U12") (pin "99") (pinfunction "PC9_99") (pintype "bidirectional"))
    )
    (net (code "117") (name "unconnected-(U12A-PC10-Pad111)") (class "Default")
      (node (ref "U12") (pin "111") (pinfunction "PC10_111") (pintype "bidirectional"))
    )
    (net (code "118") (name "unconnected-(U12A-PC11-Pad112)") (class "Default")
      (node (ref "U12") (pin "112") (pinfunction "PC11_112") (pintype "bidirectional"))
    )
    (net (code "119") (name "unconnected-(U12A-PC12-Pad113)") (class "Default")
      (node (ref "U12") (pin "113") (pinfunction "PC12_113") (pintype "bidirectional"))
    )
    (net (code "120") (name "unconnected-(U12A-PC13-Pad7)") (class "Default")
      (node (ref "U12") (pin "7") (pinfunction "PC13_7") (pintype "bidirectional"))
    )
    (net (code "121") (name "unconnected-(U12A-PC14-OSC32_IN(PC14)-Pad8)") (class "Default")
      (node (ref "U12") (pin "8") (pinfunction "PC14-OSC32_IN(PC14)_8") (pintype "bidirectional"))
    )
    (net (code "122") (name "unconnected-(U12A-PC15-OSC32_OUT(PC15)-Pad9)") (class "Default")
      (node (ref "U12") (pin "9") (pinfunction "PC15-OSC32_OUT(PC15)_9") (pintype "bidirectional"))
    )
    (net (code "123") (name "unconnected-(U12A-PD0-Pad114)") (class "Default")
      (node (ref "U12") (pin "114") (pinfunction "PD0_114") (pintype "bidirectional"))
    )
    (net (code "124") (name "unconnected-(U12A-PD1-Pad115)") (class "Default")
      (node (ref "U12") (pin "115") (pinfunction "PD1_115") (pintype "bidirectional"))
    )
    (net (code "125") (name "unconnected-(U12A-PD2-Pad116)") (class "Default")
      (node (ref "U12") (pin "116") (pinfunction "PD2_116") (pintype "bidirectional"))
    )
    (net (code "126") (name "unconnected-(U12A-PD3-Pad117)") (class "Default")
      (node (ref "U12") (pin "117") (pinfunction "PD3_117") (pintype "bidirectional"))
    )
    (net (code "127") (name "unconnected-(U12A-PD4-Pad118)") (class "Default")
      (node (ref "U12") (pin "118") (pinfunction "PD4_118") (pintype "bidirectional"))
    )
    (net (code "128") (name "unconnected-(U12A-PD5-Pad119)") (class "Default")
      (node (ref "U12") (pin "119") (pinfunction "PD5_119") (pintype "bidirectional"))
    )
    (net (code "129") (name "unconnected-(U12A-PD6-Pad122)") (class "Default")
      (node (ref "U12") (pin "122") (pinfunction "PD6_122") (pintype "bidirectional"))
    )
    (net (code "130") (name "unconnected-(U12A-PD7-Pad123)") (class "Default")
      (node (ref "U12") (pin "123") (pinfunction "PD7_123") (pintype "bidirectional"))
    )
    (net (code "131") (name "unconnected-(U12A-PD8-Pad77)") (class "Default")
      (node (ref "U12") (pin "77") (pinfunction "PD8_77") (pintype "bidirectional"))
    )
    (net (code "132") (name "unconnected-(U12A-PD9-Pad78)") (class "Default")
      (node (ref "U12") (pin "78") (pinfunction "PD9_78") (pintype "bidirectional"))
    )
    (net (code "133") (name "unconnected-(U12A-PD10-Pad79)") (class "Default")
      (node (ref "U12") (pin "79") (pinfunction "PD10_79") (pintype "bidirectional"))
    )
    (net (code "134") (name "unconnected-(U12A-PD11-Pad80)") (class "Default")
      (node (ref "U12") (pin "80") (pinfunction "PD11_80") (pintype "bidirectional"))
    )
    (net (code "135") (name "unconnected-(U12A-PD12-Pad81)") (class "Default")
      (node (ref "U12") (pin "81") (pinfunction "PD12_81") (pintype "bidirectional"))
    )
    (net (code "136") (name "unconnected-(U12A-PD13-Pad82)") (class "Default")
      (node (ref "U12") (pin "82") (pinfunction "PD13_82") (pintype "bidirectional"))
    )
    (net (code "137") (name "unconnected-(U12A-PD14-Pad85)") (class "Default")
      (node (ref "U12") (pin "85") (pinfunction "PD14_85") (pintype "bidirectional"))
    )
    (net (code "138") (name "unconnected-(U12A-PD15-Pad86)") (class "Default")
      (node (ref "U12") (pin "86") (pinfunction "PD15_86") (pintype "bidirectional"))
    )
    (net (code "139") (name "unconnected-(U12B-BOOT0-Pad138)") (class "Default")
      (node (ref "U12") (pin "138") (pinfunction "BOOT0_138") (pintype "input"))
    )
    (net (code "140") (name "unconnected-(U12B-NRST-Pad25)") (class "Default")
      (node (ref "U12") (pin "25") (pinfunction "NRST_25") (pintype "bidirectional"))
    )
    (net (code "141") (name "unconnected-(U12B-PDR_ON-Pad143)") (class "Default")
      (node (ref "U12") (pin "143") (pinfunction "PDR_ON_143") (pintype "input"))
    )
    (net (code "142") (name "unconnected-(U12B-PE0-Pad141)") (class "Default")
      (node (ref "U12") (pin "141") (pinfunction "PE0_141") (pintype "bidirectional"))
    )
    (net (code "143") (name "unconnected-(U12B-PE1-Pad142)") (class "Default")
      (node (ref "U12") (pin "142") (pinfunction "PE1_142") (pintype "bidirectional"))
    )
    (net (code "144") (name "unconnected-(U12B-PE2-Pad1)") (class "Default")
      (node (ref "U12") (pin "1") (pinfunction "PE2_1") (pintype "bidirectional"))
    )
    (net (code "145") (name "unconnected-(U12B-PE3-Pad2)") (class "Default")
      (node (ref "U12") (pin "2") (pinfunction "PE3_2") (pintype "bidirectional"))
    )
    (net (code "146") (name "unconnected-(U12B-PE4-Pad3)") (class "Default")
      (node (ref "U12") (pin "3") (pinfunction "PE4_3") (pintype "bidirectional"))
    )
    (net (code "147") (name "unconnected-(U12B-PE5-Pad4)") (class "Default")
      (node (ref "U12") (pin "4") (pinfunction "PE5_4") (pintype "bidirectional"))
    )
    (net (code "148") (name "unconnected-(U12B-PE6-Pad5)") (class "Default")
      (node (ref "U12") (pin "5") (pinfunction "PE6_5") (pintype "bidirectional"))
    )
    (net (code "149") (name "unconnected-(U12B-PE7-Pad58)") (class "Default")
      (node (ref "U12") (pin "58") (pinfunction "PE7_58") (pintype "bidirectional"))
    )
    (net (code "150") (name "unconnected-(U12B-PE8-Pad59)") (class "Default")
      (node (ref "U12") (pin "59") (pinfunction "PE8_59") (pintype "bidirectional"))
    )
    (net (code "151") (name "unconnected-(U12B-PE9-Pad60)") (class "Default")
      (node (ref "U12") (pin "60") (pinfunction "PE9_60") (pintype "bidirectional"))
    )
    (net (code "152") (name "unconnected-(U12B-PE10-Pad63)") (class "Default")
      (node (ref "U12") (pin "63") (pinfunction "PE10_63") (pintype "bidirectional"))
    )
    (net (code "153") (name "unconnected-(U12B-PE11-Pad64)") (class "Default")
      (node (ref "U12") (pin "64") (pinfunction "PE11_64") (pintype "bidirectional"))
    )
    (net (code "154") (name "unconnected-(U12B-PE12-Pad65)") (class "Default")
      (node (ref "U12") (pin "65") (pinfunction "PE12_65") (pintype "bidirectional"))
    )
    (net (code "155") (name "unconnected-(U12B-PE13-Pad66)") (class "Default")
      (node (ref "U12") (pin "66") (pinfunction "PE13_66") (pintype "bidirectional"))
    )
    (net (code "156") (name "unconnected-(U12B-PE14-Pad67)") (class "Default")
      (node (ref "U12") (pin "67") (pinfunction "PE14_67") (pintype "bidirectional"))
    )
    (net (code "157") (name "unconnected-(U12B-PE15-Pad68)") (class "Default")
      (node (ref "U12") (pin "68") (pinfunction "PE15_68") (pintype "bidirectional"))
    )
    (net (code "158") (name "unconnected-(U12B-PF0-Pad10)") (class "Default")
      (node (ref "U12") (pin "10") (pinfunction "PF0_10") (pintype "bidirectional"))
    )
    (net (code "159") (name "unconnected-(U12B-PF1-Pad11)") (class "Default")
      (node (ref "U12") (pin "11") (pinfunction "PF1_11") (pintype "bidirectional"))
    )
    (net (code "160") (name "unconnected-(U12B-PF2-Pad12)") (class "Default")
      (node (ref "U12") (pin "12") (pinfunction "PF2_12") (pintype "bidirectional"))
    )
    (net (code "161") (name "unconnected-(U12B-PF3-Pad13)") (class "Default")
      (node (ref "U12") (pin "13") (pinfunction "PF3_13") (pintype "bidirectional"))
    )
    (net (code "162") (name "unconnected-(U12B-PF4-Pad14)") (class "Default")
      (node (ref "U12") (pin "14") (pinfunction "PF4_14") (pintype "bidirectional"))
    )
    (net (code "163") (name "unconnected-(U12B-PF5-Pad15)") (class "Default")
      (node (ref "U12") (pin "15") (pinfunction "PF5_15") (pintype "bidirectional"))
    )
    (net (code "164") (name "unconnected-(U12B-PF6-Pad18)") (class "Default")
      (node (ref "U12") (pin "18") (pinfunction "PF6_18") (pintype "bidirectional"))
    )
    (net (code "165") (name "unconnected-(U12B-PF7-Pad19)") (class "Default")
      (node (ref "U12") (pin "19") (pinfunction "PF7_19") (pintype "bidirectional"))
    )
    (net (code "166") (name "unconnected-(U12B-PF8-Pad20)") (class "Default")
      (node (ref "U12") (pin "20") (pinfunction "PF8_20") (pintype "bidirectional"))
    )
    (net (code "167") (name "unconnected-(U12B-PF9-Pad21)") (class "Default")
      (node (ref "U12") (pin "21") (pinfunction "PF9_21") (pintype "bidirectional"))
    )
    (net (code "168") (name "unconnected-(U12B-PF10-Pad22)") (class "Default")
      (node (ref "U12") (pin "22") (pinfunction "PF10_22") (pintype "bidirectional"))
    )
    (net (code "169") (name "unconnected-(U12B-PF11-Pad49)") (class "Default")
      (node (ref "U12") (pin "49") (pinfunction "PF11_49") (pintype "bidirectional"))
    )
    (net (code "170") (name "unconnected-(U12B-PF12-Pad50)") (class "Default")
      (node (ref "U12") (pin "50") (pinfunction "PF12_50") (pintype "bidirectional"))
    )
    (net (code "171") (name "unconnected-(U12B-PF13-Pad53)") (class "Default")
      (node (ref "U12") (pin "53") (pinfunction "PF13_53") (pintype "bidirectional"))
    )
    (net (code "172") (name "unconnected-(U12B-PF14-Pad54)") (class "Default")
      (node (ref "U12") (pin "54") (pinfunction "PF14_54") (pintype "bidirectional"))
    )
    (net (code "173") (name "unconnected-(U12B-PF15-Pad55)") (class "Default")
      (node (ref "U12") (pin "55") (pinfunction "PF15_55") (pintype "bidirectional"))
    )
    (net (code "174") (name "unconnected-(U12B-PG0-Pad56)") (class "Default")
      (node (ref "U12") (pin "56") (pinfunction "PG0_56") (pintype "bidirectional"))
    )
    (net (code "175") (name "unconnected-(U12B-PG1-Pad57)") (class "Default")
      (node (ref "U12") (pin "57") (pinfunction "PG1_57") (pintype "bidirectional"))
    )
    (net (code "176") (name "unconnected-(U12B-PG2-Pad87)") (class "Default")
      (node (ref "U12") (pin "87") (pinfunction "PG2_87") (pintype "bidirectional"))
    )
    (net (code "177") (name "unconnected-(U12B-PG3-Pad88)") (class "Default")
      (node (ref "U12") (pin "88") (pinfunction "PG3_88") (pintype "bidirectional"))
    )
    (net (code "178") (name "unconnected-(U12B-PG4-Pad89)") (class "Default")
      (node (ref "U12") (pin "89") (pinfunction "PG4_89") (pintype "bidirectional"))
    )
    (net (code "179") (name "unconnected-(U12B-PG5-Pad90)") (class "Default")
      (node (ref "U12") (pin "90") (pinfunction "PG5_90") (pintype "bidirectional"))
    )
    (net (code "180") (name "unconnected-(U12B-PG6-Pad91)") (class "Default")
      (node (ref "U12") (pin "91") (pinfunction "PG6_91") (pintype "bidirectional"))
    )
    (net (code "181") (name "unconnected-(U12B-PG7-Pad92)") (class "Default")
      (node (ref "U12") (pin "92") (pinfunction "PG7_92") (pintype "bidirectional"))
    )
    (net (code "182") (name "unconnected-(U12B-PG8-Pad93)") (class "Default")
      (node (ref "U12") (pin "93") (pinfunction "PG8_93") (pintype "bidirectional"))
    )
    (net (code "183") (name "unconnected-(U12B-PG9-Pad124)") (class "Default")
      (node (ref "U12") (pin "124") (pinfunction "PG9_124") (pintype "bidirectional"))
    )
    (net (code "184") (name "unconnected-(U12B-PG10-Pad125)") (class "Default")
      (node (ref "U12") (pin "125") (pinfunction "PG10_125") (pintype "bidirectional"))
    )
    (net (code "185") (name "unconnected-(U12B-PG11-Pad126)") (class "Default")
      (node (ref "U12") (pin "126") (pinfunction "PG11_126") (pintype "bidirectional"))
    )
    (net (code "186") (name "unconnected-(U12B-PG12-Pad127)") (class "Default")
      (node (ref "U12") (pin "127") (pinfunction "PG12_127") (pintype "bidirectional"))
    )
    (net (code "187") (name "unconnected-(U12B-PG13-Pad128)") (class "Default")
      (node (ref "U12") (pin "128") (pinfunction "PG13_128") (pintype "bidirectional"))
    )
    (net (code "188") (name "unconnected-(U12B-PG14-Pad129)") (class "Default")
      (node (ref "U12") (pin "129") (pinfunction "PG14_129") (pintype "bidirectional"))
    )
    (net (code "189") (name "unconnected-(U12B-PG15-Pad132)") (class "Default")
      (node (ref "U12") (pin "132") (pinfunction "PG15_132") (pintype "bidirectional"))
    )
    (net (code "190") (name "unconnected-(U12B-PH0-OSC_IN(PH0)-Pad23)") (class "Default")
      (node (ref "U12") (pin "23") (pinfunction "PH0-OSC_IN(PH0)_23") (pintype "bidirectional"))
    )
    (net (code "191") (name "unconnected-(U12B-PH1-OSC_OUT(PH1)-Pad24)") (class "Default")
      (node (ref "U12") (pin "24") (pinfunction "PH1-OSC_OUT(PH1)_24") (pintype "bidirectional"))
    )
    (net (code "192") (name "unconnected-(U12B-VCAP_1-Pad71)") (class "Default")
      (node (ref "U12") (pin "71") (pinfunction "VCAP_1_71") (pintype "power_in"))
    )
    (net (code "193") (name "unconnected-(U12B-VCAP_2-Pad106)") (class "Default")
      (node (ref "U12") (pin "106") (pinfunction "VCAP_2_106") (pintype "power_in"))
    )
    (net (code "194") (name "unconnected-(U12C-VBAT-Pad6)") (class "Default")
      (node (ref "U12") (pin "6") (pinfunction "VBAT_6") (pintype "power_in"))
    )
    (net (code "195") (name "unconnected-(U12C-VDD-Pad17)") (class "Default")
      (node (ref "U12") (pin "17") (pinfunction "VDD_17") (pintype "power_in"))
    )
    (net (code "196") (name "unconnected-(U12C-VDD-Pad30)") (class "Default")
      (node (ref "U12") (pin "30") (pinfunction "VDD_30") (pintype "power_in"))
    )
    (net (code "197") (name "unconnected-(U12C-VDD-Pad39)") (class "Default")
      (node (ref "U12") (pin "39") (pinfunction "VDD_39") (pintype "power_in"))
    )
    (net (code "198") (name "unconnected-(U12C-VDD-Pad52)") (class "Default")
      (node (ref "U12") (pin "52") (pinfunction "VDD_52") (pintype "power_in"))
    )
    (net (code "199") (name "unconnected-(U12C-VDD-Pad62)") (class "Default")
      (node (ref "U12") (pin "62") (pinfunction "VDD_62") (pintype "power_in"))
    )
    (net (code "200") (name "unconnected-(U12C-VDD-Pad72)") (class "Default")
      (node (ref "U12") (pin "72") (pinfunction "VDD_72") (pintype "power_in"))
    )
    (net (code "201") (name "unconnected-(U12C-VDD-Pad84)") (class "Default")
      (node (ref "U12") (pin "84") (pinfunction "VDD_84") (pintype "power_in"))
    )
    (net (code "202") (name "unconnected-(U12C-VDD-Pad95)") (class "Default")
      (node (ref "U12") (pin "95") (pinfunction "VDD_95") (pintype "power_in"))
    )
    (net (code "203") (name "unconnected-(U12C-VDD-Pad108)") (class "Default")
      (node (ref "U12") (pin "108") (pinfunction "VDD_108") (pintype "power_in"))
    )
    (net (code "204") (name "unconnected-(U12C-VDD-Pad121)") (class "Default")
      (node (ref "U12") (pin "121") (pinfunction "VDD_121") (pintype "power_in"))
    )
    (net (code "205") (name "unconnected-(U12C-VDD-Pad131)") (class "Default")
      (node (ref "U12") (pin "131") (pinfunction "VDD_131") (pintype "power_in"))
    )
    (net (code "206") (name "unconnected-(U12C-VDD-Pad144)") (class "Default")
      (node (ref "U12") (pin "144") (pinfunction "VDD_144") (pintype "power_in"))
    )
    (net (code "207") (name "unconnected-(U12C-VDDA-Pad33)") (class "Default")
      (node (ref "U12") (pin "33") (pinfunction "VDDA_33") (pintype "power_in"))
    )
    (net (code "208") (name "unconnected-(U12C-VREF+-Pad32)") (class "Default")
      (node (ref "U12") (pin "32") (pinfunction "VREF+_32") (pintype "power_in"))
    )
    (net (code "209") (name "unconnected-(U12C-VSS-Pad16)") (class "Default")
      (node (ref "U12") (pin "16") (pinfunction "VSS_16") (pintype "power_in"))
    )
    (net (code "210") (name "unconnected-(U12C-VSS-Pad38)") (class "Default")
      (node (ref "U12") (pin "38") (pinfunction "VSS_38") (pintype "power_in"))
    )
    (net (code "211") (name "unconnected-(U12C-VSS-Pad51)") (class "Default")
      (node (ref "U12") (pin "51") (pinfunction "VSS_51") (pintype "power_in"))
    )
    (net (code "212") (name "unconnected-(U12C-VSS-Pad61)") (class "Default")
      (node (ref "U12") (pin "61") (pinfunction "VSS_61") (pintype "power_in"))
    )
    (net (code "213") (name "unconnected-(U12C-VSS-Pad83)") (class "Default")
      (node (ref "U12") (pin "83") (pinfunction "VSS_83") (pintype "power_in"))
    )
    (net (code "214") (name "unconnected-(U12C-VSS-Pad94)") (class "Default")
      (node (ref "U12") (pin "94") (pinfunction "VSS_94") (pintype "power_in"))
    )
    (net (code "215") (name "unconnected-(U12C-VSS-Pad107)") (class "Default")
      (node (ref "U12") (pin "107") (pinfunction "VSS_107") (pintype "power_in"))
    )
    (net (code "216") (name "unconnected-(U12C-VSS-Pad120)") (class "Default")
      (node (ref "U12") (pin "120") (pinfunction "VSS_120") (pintype "power_in"))
    )
    (net (code "217") (name "unconnected-(U12C-VSS-Pad130)") (class "Default")
      (node (ref "U12") (pin "130") (pinfunction "VSS_130") (pintype "power_in"))
    )
    (net (code "218") (name "unconnected-(U12C-VSSA-Pad31)") (class "Default")
      (node (ref "U12") (pin "31") (pinfunction "VSSA_31") (pintype "power_in"))
    )
  )
)
